# SensX3N.net
KiCad netlist of a schematic drawn in EAGLE
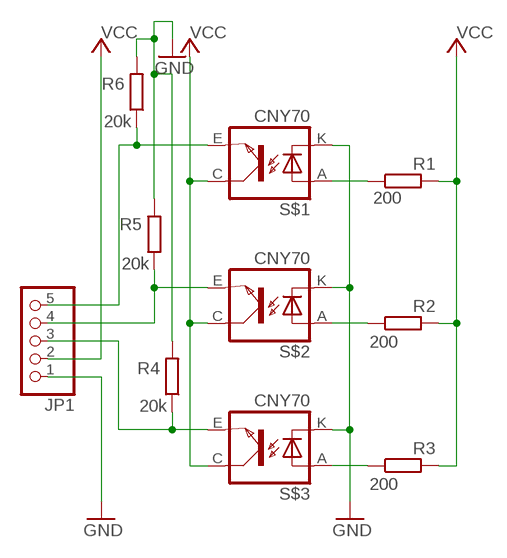
[diagram p0: schematic, sheet 1]

(export (version "E")
  (design (tool "Eeschema 10.0.6"))
  (components
    (comp (ref "JP1")
      (value "PINHD-1X5")
      (footprint "eagle-import:1X05")
      (libsource (lib "eagle-import") (part "PINHD-1X5"))
    )
    (comp (ref "R1")
      (value "200")
      (footprint "eagle-import:R0805")
      (libsource (lib "eagle-import") (part "R-EU_R0805"))
    )
    (comp (ref "R2")
      (value "200")
      (footprint "eagle-import:R0805")
      (libsource (lib "eagle-import") (part "R-EU_R0805"))
    )
    (comp (ref "R3")
      (value "200")
      (footprint "eagle-import:R0805")
      (libsource (lib "eagle-import") (part "R-EU_R0805"))
    )
    (comp (ref "R4")
      (value "20k")
      (footprint "eagle-import:R0805")
      (libsource (lib "eagle-import") (part "R-EU_R0805"))
    )
    (comp (ref "R5")
      (value "20k")
      (footprint "eagle-import:R0805")
      (libsource (lib "eagle-import") (part "R-EU_R0805"))
    )
    (comp (ref "R6")
      (value "20k")
      (footprint "eagle-import:R0805")
      (libsource (lib "eagle-import") (part "R-EU_R0805"))
    )
    (comp (ref "S$1")
      (value "CNY70")
      (footprint "eagle-import:4")
      (libsource (lib "eagle-import") (part "CNY70"))
    )
    (comp (ref "S$2")
      (value "CNY70")
      (footprint "eagle-import:4")
      (libsource (lib "eagle-import") (part "CNY70"))
    )
    (comp (ref "S$3")
      (value "CNY70")
      (footprint "eagle-import:4")
      (libsource (lib "eagle-import") (part "CNY70"))
    )
  )
  (nets
    (net (code "1") (name "GND") (class "Default")
      (node (ref "JP1") (pin "1") (pinfunction "1_1") (pintype "passive"))
      (node (ref "R4") (pin "2") (pinfunction "2_2") (pintype "passive"))
      (node (ref "R5") (pin "2") (pinfunction "2_2") (pintype "passive"))
      (node (ref "R6") (pin "2") (pinfunction "2_2") (pintype "passive"))
      (node (ref "S$1") (pin "K") (pinfunction "C_K") (pintype "passive"))
      (node (ref "S$2") (pin "K") (pinfunction "C_K") (pintype "passive"))
      (node (ref "S$3") (pin "K") (pinfunction "C_K") (pintype "passive"))
    )
    (net (code "2") (name "Net-(R1-Pad1)") (class "Default")
      (node (ref "R1") (pin "1") (pinfunction "1_1") (pintype "passive"))
      (node (ref "S$1") (pin "A") (pinfunction "A_A") (pintype "passive"))
    )
    (net (code "3") (name "Net-(R2-Pad1)") (class "Default")
      (node (ref "R2") (pin "1") (pinfunction "1_1") (pintype "passive"))
      (node (ref "S$2") (pin "A") (pinfunction "A_A") (pintype "passive"))
    )
    (net (code "4") (name "Net-(R3-Pad1)") (class "Default")
      (node (ref "R3") (pin "1") (pinfunction "1_1") (pintype "passive"))
      (node (ref "S$3") (pin "A") (pinfunction "A_A") (pintype "passive"))
    )
    (net (code "5") (name "Net-(S$1-EMI)") (class "Default")
      (node (ref "JP1") (pin "5") (pinfunction "5_5") (pintype "passive"))
      (node (ref "R6") (pin "1") (pinfunction "1_1") (pintype "passive"))
      (node (ref "S$1") (pin "E") (pinfunction "EMI_E") (pintype "passive"))
    )
    (net (code "6") (name "Net-(S$2-EMI)") (class "Default")
      (node (ref "JP1") (pin "4") (pinfunction "4_4") (pintype "passive"))
      (node (ref "R5") (pin "1") (pinfunction "1_1") (pintype "passive"))
      (node (ref "S$2") (pin "E") (pinfunction "EMI_E") (pintype "passive"))
    )
    (net (code "7") (name "Net-(S$3-EMI)") (class "Default")
      (node (ref "JP1") (pin "3") (pinfunction "3_3") (pintype "passive"))
      (node (ref "R4") (pin "1") (pinfunction "1_1") (pintype "passive"))
      (node (ref "S$3") (pin "E") (pinfunction "EMI_E") (pintype "passive"))
    )
    (net (code "8") (name "VCC") (class "Default")
      (node (ref "JP1") (pin "2") (pinfunction "2_2") (pintype "passive"))
      (node (ref "R1") (pin "2") (pinfunction "2_2") (pintype "passive"))
      (node (ref "R2") (pin "2") (pinfunction "2_2") (pintype "passive"))
      (node (ref "R3") (pin "2") (pinfunction "2_2") (pintype "passive"))
      (node (ref "S$1") (pin "C") (pinfunction "COL_C") (pintype "passive"))
      (node (ref "S$2") (pin "C") (pinfunction "COL_C") (pintype "passive"))
      (node (ref "S$3") (pin "C") (pinfunction "COL_C") (pintype "passive"))
    )
  )
)
